# 51.net
KiCad netlist of a schematic drawn in EasyEDA Pro
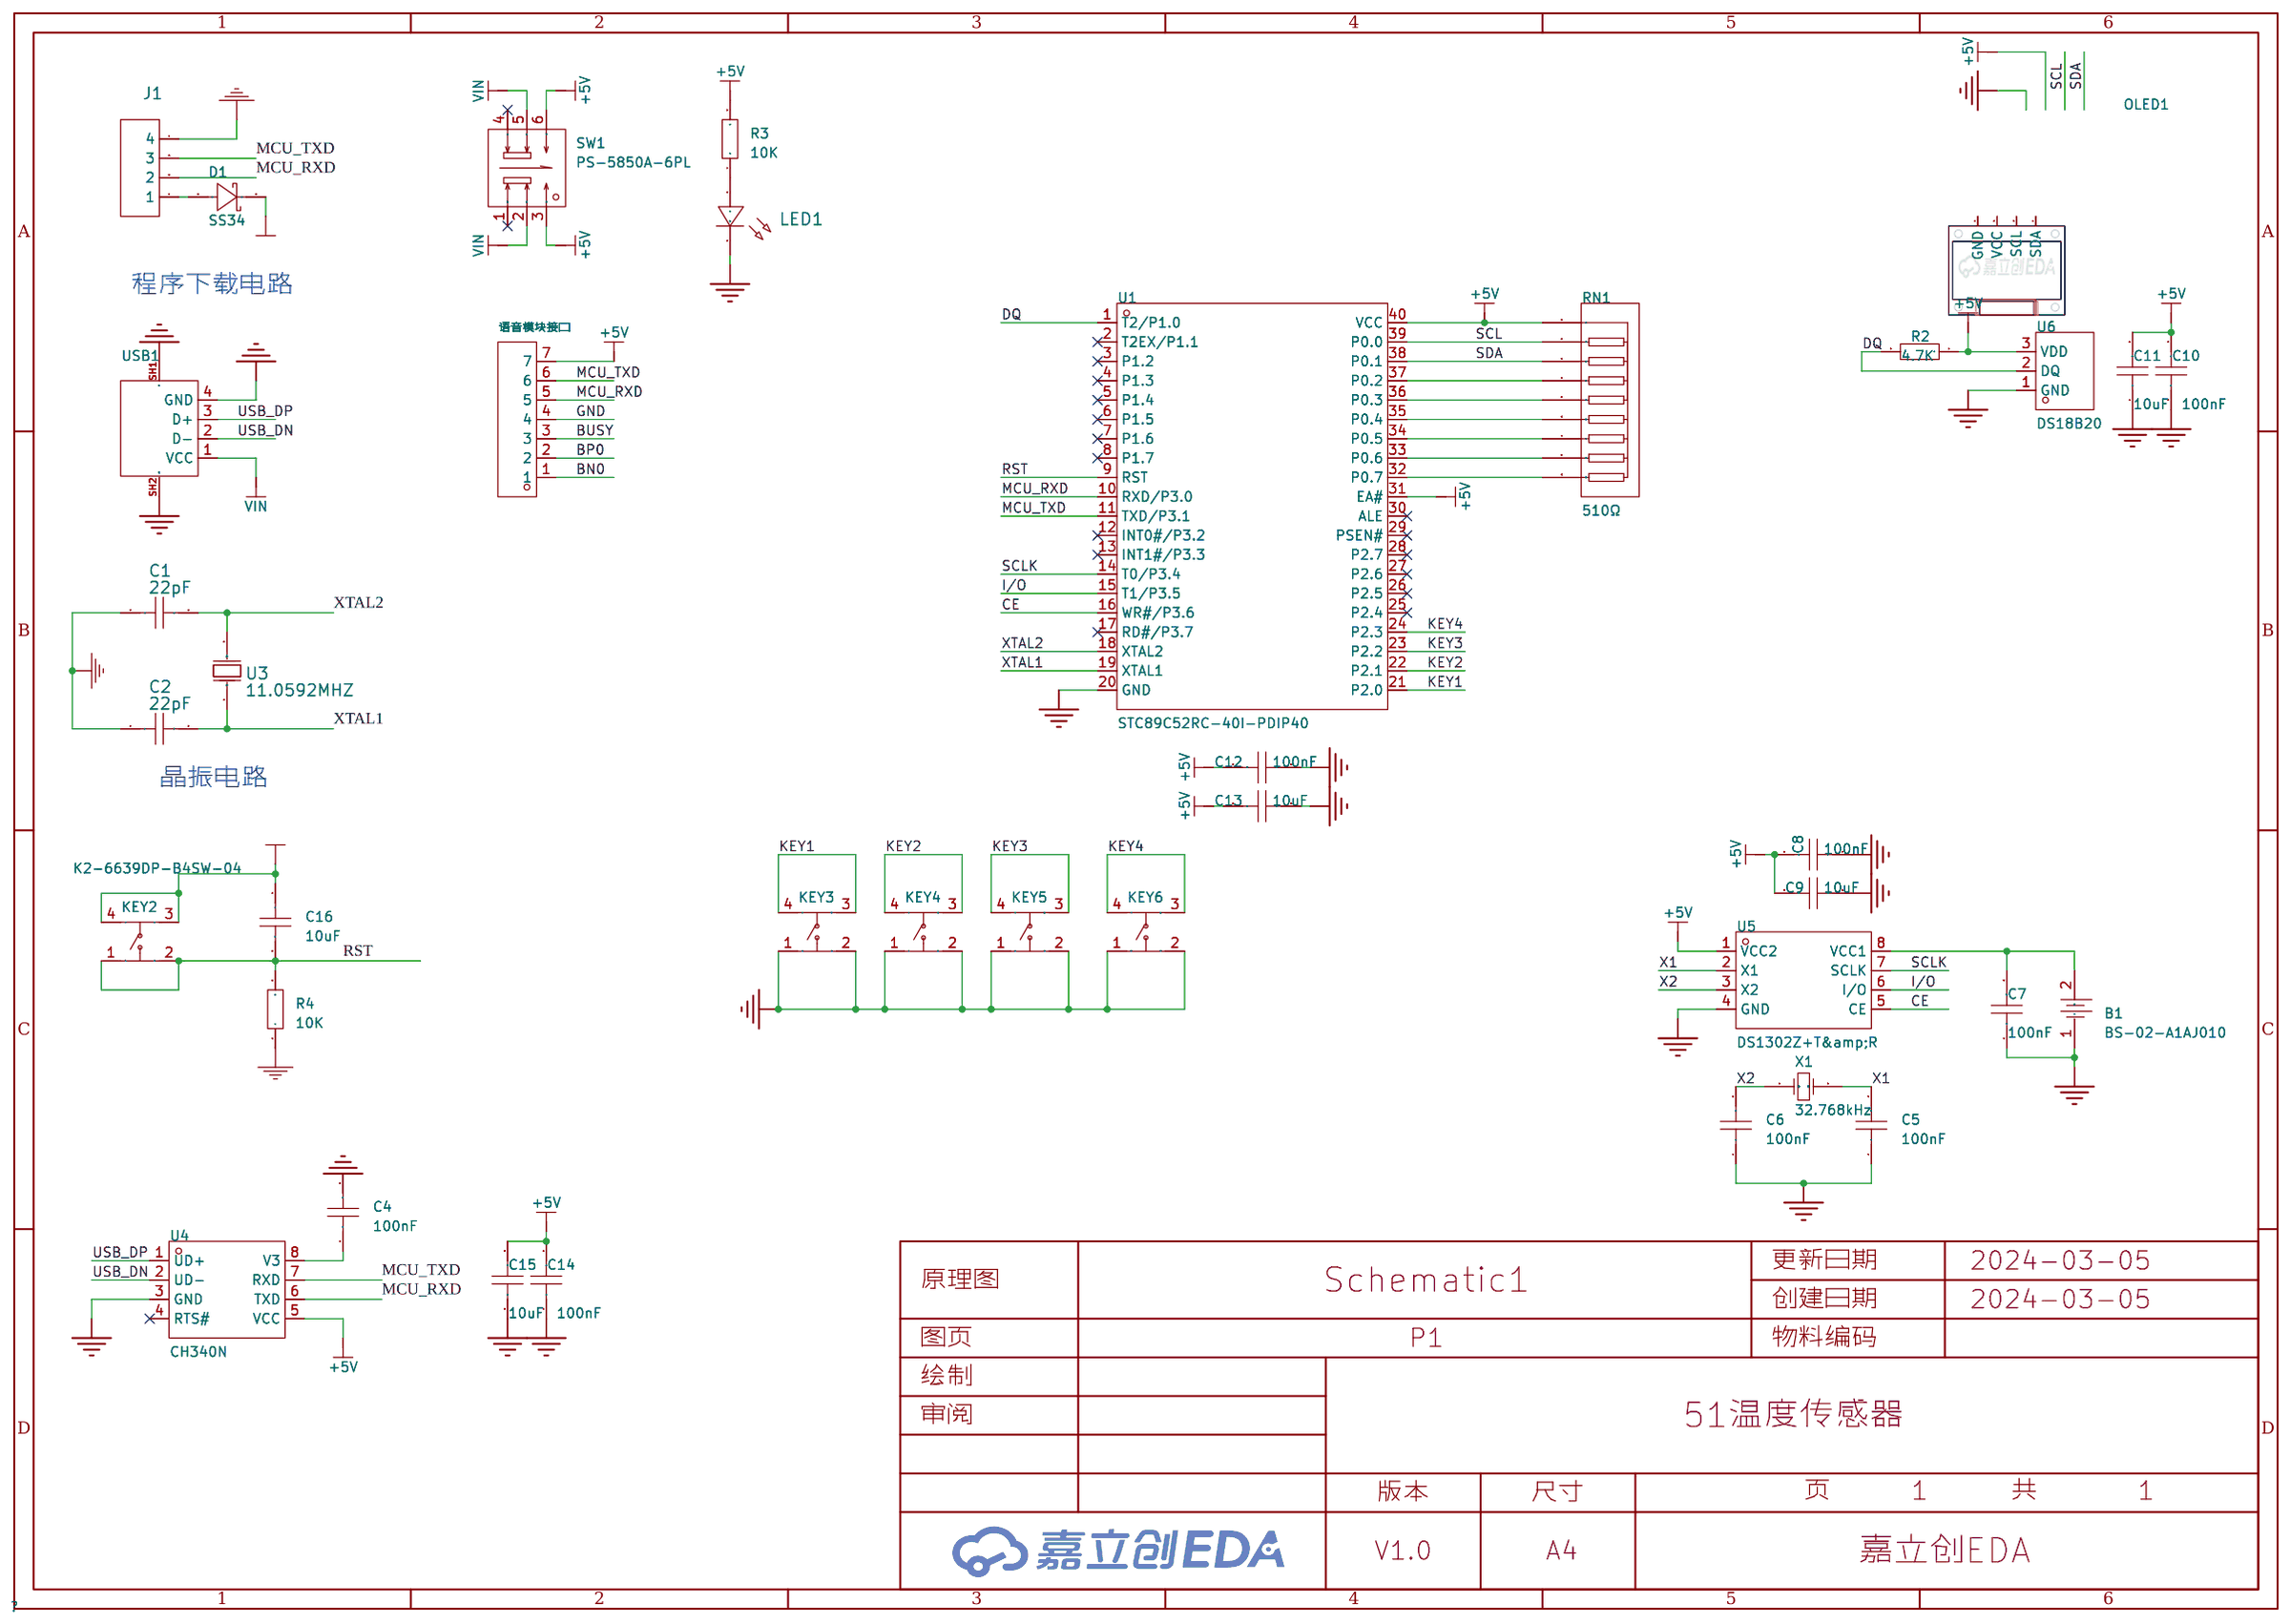
[diagram p0: schematic sheet]

(export (version "E")
  (design (tool "Eeschema 10.0.6"))
  (components
    (comp (ref "B1")
      (value "BS-02-A1AJ010")
      (footprint "easyedapro:BAT-TH_BS-02-A1AJ010")
      (description "连接器类型:电池底座;适用电池规格:CR2032;工作温度范围:-25°C~+85°C;")
      (fields (field (name "Manufacturer") "MYOUNG(美阳)"))
      (libsource (lib "easyedapro") (part "BS-02-A1AJ010"))
    )
    (comp (ref "C1")
      (value "22pF")
      (footprint "easyedapro:C0603")
      (libsource (lib "easyedapro") (part "22pF"))
    )
    (comp (ref "C2")
      (value "22pF")
      (footprint "easyedapro:C0603")
      (libsource (lib "easyedapro") (part "22pF"))
    )
    (comp (ref "C4")
      (value "100nF")
      (footprint "easyedapro:C0603")
      (libsource (lib "easyedapro") (part "CapAcitance"))
    )
    (comp (ref "C5")
      (value "100nF")
      (footprint "easyedapro:C0603")
      (libsource (lib "easyedapro") (part "CapAcitance"))
    )
    (comp (ref "C6")
      (value "100nF")
      (footprint "easyedapro:C0603")
      (libsource (lib "easyedapro") (part "CapAcitance"))
    )
    (comp (ref "C7")
      (value "100nF")
      (footprint "easyedapro:C0603")
      (libsource (lib "easyedapro") (part "CapAcitance"))
    )
    (comp (ref "C8")
      (value "100nF")
      (footprint "easyedapro:C0603")
      (libsource (lib "easyedapro") (part "CapAcitance"))
    )
    (comp (ref "C9")
      (value "10uF")
      (footprint "easyedapro:C0603")
      (libsource (lib "easyedapro") (part "CapAcitance"))
    )
    (comp (ref "C10")
      (value "100nF")
      (footprint "easyedapro:C0603")
      (libsource (lib "easyedapro") (part "CapAcitance"))
    )
    (comp (ref "C11")
      (value "10uF")
      (footprint "easyedapro:C0603")
      (libsource (lib "easyedapro") (part "CapAcitance"))
    )
    (comp (ref "C12")
      (value "100nF")
      (footprint "easyedapro:C0603")
      (libsource (lib "easyedapro") (part "CapAcitance"))
    )
    (comp (ref "C13")
      (value "10uF")
      (footprint "easyedapro:C0603")
      (libsource (lib "easyedapro") (part "CapAcitance"))
    )
    (comp (ref "C14")
      (value "100nF")
      (footprint "easyedapro:C0603")
      (libsource (lib "easyedapro") (part "CapAcitance"))
    )
    (comp (ref "C15")
      (value "10uF")
      (footprint "easyedapro:C0603")
      (libsource (lib "easyedapro") (part "CapAcitance"))
    )
    (comp (ref "C16")
      (value "10uF")
      (footprint "easyedapro:C0603")
      (libsource (lib "easyedapro") (part "CapAcitance"))
    )
    (comp (ref "D1")
      (value "SS34")
      (footprint "easyedapro:SMA_L4.3-W2.5-LS5.0-RD")
      (description "二极管配置:独立式;正向压降(Vf):550mV@3A;直流反向耐压(Vr):40V;平均整流电流(Io):3A;")
      (fields (field (name "Manufacturer") "TWGMC(台湾迪嘉)"))
      (libsource (lib "easyedapro") (part "SS34_C727060"))
    )
    (comp (ref "J1")
      (value "HDR-M-2.54_1x4")
      (footprint "easyedapro:HDR-M-2.54_1X4")
      (libsource (lib "easyedapro") (part "HDR-M-2.54_1x4"))
    )
    (comp (ref "KEY2")
      (value "K2-6639DP-B4SW-04")
      (footprint "easyedapro:KEY-TH_4P-L6.0-W6.0-P3.90-LS7.8")
      (fields (field (name "Manufacturer") "韩国韩荣"))
      (libsource (lib "easyedapro") (part "K2-6639DP-B4SW-04"))
    )
    (comp (ref "KEY3")
      (value "K2-6639DP-B4SW-04")
      (footprint "easyedapro:KEY-TH_4P-L6.0-W6.0-P3.90-LS7.8")
      (fields (field (name "Manufacturer") "韩国韩荣"))
      (libsource (lib "easyedapro") (part "K2-6639DP-B4SW-04"))
    )
    (comp (ref "KEY4")
      (value "K2-6639DP-B4SW-04")
      (footprint "easyedapro:KEY-TH_4P-L6.0-W6.0-P3.90-LS7.8")
      (fields (field (name "Manufacturer") "韩国韩荣"))
      (libsource (lib "easyedapro") (part "K2-6639DP-B4SW-04"))
    )
    (comp (ref "KEY5")
      (value "K2-6639DP-B4SW-04")
      (footprint "easyedapro:KEY-TH_4P-L6.0-W6.0-P3.90-LS7.8")
      (fields (field (name "Manufacturer") "韩国韩荣"))
      (libsource (lib "easyedapro") (part "K2-6639DP-B4SW-04"))
    )
    (comp (ref "KEY6")
      (value "K2-6639DP-B4SW-04")
      (footprint "easyedapro:KEY-TH_4P-L6.0-W6.0-P3.90-LS7.8")
      (fields (field (name "Manufacturer") "韩国韩荣"))
      (libsource (lib "easyedapro") (part "K2-6639DP-B4SW-04"))
    )
    (comp (ref "LED1")
      (value "~")
      (footprint "easyedapro:LED_0603")
      (libsource (lib "easyedapro") (part "LED_R"))
    )
    (comp (ref "OLED1")
      (value "~")
      (footprint "easyedapro:0.96OLED_4P")
      (libsource (lib "easyedapro") (part "0.96OLED模块_4P"))
    )
    (comp (ref "R2") (value "4.7K") (footprint "easyedapro:R0603") (libsource (lib "easyedapro") (part "电阻")))
    (comp (ref "R3") (value "10K") (footprint "easyedapro:R0603") (libsource (lib "easyedapro") (part "电阻")))
    (comp (ref "R4") (value "10K") (footprint "easyedapro:R0603") (libsource (lib "easyedapro") (part "电阻")))
    (comp (ref "RN1")
      (value "510Ω")
      (footprint "easyedapro:RES-ARRAY-TH_9P-P2.54-D1.0")
      (description "电阻器数:8;阻值:510Ω;精度:±5%;单个元件功率:125mW;温度系数:±100ppm/°C;")
      (fields (field (name "Manufacturer Part") "A09-511JP") (field (name "Manufacturer") "FH(风华)"))
      (libsource (lib "easyedapro") (part "A09-511J"))
    )
    (comp (ref "SW1")
      (value "PS-5850A-6PL")
      (footprint "easyedapro:SW-TH_6P-L5.8-W5.8-P2.00-LS4.5-BL")
      (description "5.8自锁按键开关 高头 耐高温")
      (fields (field (name "Manufacturer") "G-Switch(品赞)"))
      (libsource (lib "easyedapro") (part "PS-5850A-6PL"))
    )
    (comp (ref "U1")
      (value "STC89C52RC-40I-PDIP40")
      (footprint "easyedapro:DIP-40_L52.0-W13.7-P2.54-LS15.2-BL")
      (description "CPU内核:51系列;程序存储容量:8KB;RAM总容量:512Byte;GPIO端口数量:35;工作电压范围:3.3V~5.5V;CPU最大主频:-;程序存储器类型:FLASH;")
      (fields (field (name "Manufacturer") "STC(宏晶)"))
      (libsource (lib "easyedapro") (part "STC89C52RC-40I"))
    )
    (comp (ref "U3")
      (value "11.0592MHZ")
      (footprint "easyedapro:HC-49US_L11.5-W4.5-P4.88")
      (fields (field (name "Manufacturer Part") "9B-11.0592MAAJ-B") (field (name "Manufacturer") "TXC(台湾晶技)"))
      (libsource (lib "easyedapro") (part "11.0592MHZ"))
    )
    (comp (ref "U4")
      (value "CH340N")
      (footprint "easyedapro:SOP-8_L5.0-W4.0-P1.27-LS6.0-BL")
      (description "应用功能:-;接口协议:-;")
      (fields (field (name "Manufacturer") "WCH(南京沁恒)"))
      (libsource (lib "easyedapro") (part "CH340N"))
    )
    (comp (ref "U5")
      (value "DS1302Z+T&amp;R")
      (footprint "easyedapro:SOIC-8_L4.9-W3.9-P1.27-LS6.0-BL")
      (description "接口:SPI;")
      (fields (field (name "Manufacturer") "ADI(亚德诺)/MAXIM(美信)"))
      (libsource (lib "easyedapro") (part "DS1302ZN+"))
    )
    (comp (ref "U6")
      (value "DS18B20")
      (footprint "easyedapro:TO-92-3_L4.9-W3.7-P1.27-L")
      (description "温度范围:-55°C~+125°C;精度:±0.4°C;接口类型:-;")
      (fields (field (name "Manufacturer") "MSKSEMI(美森科)"))
      (libsource (lib "easyedapro") (part "DS18B20_C5379069"))
    )
    (comp (ref "USB1")
      (value "~")
      (footprint "easyedapro:USB_ Type-A")
      (libsource (lib "easyedapro") (part "USB_Type-A"))
    )
    (comp (ref "X1")
      (value "32.768kHz")
      (footprint "easyedapro:OSC-TH_BD1.0-P0.50")
      (description "晶振类型:直插晶振;频率:32.768kHz;常温频差:±20ppm;外接负载电容:12.5pF;频率稳定度(全温):±20ppm;")
      (fields (field (name "Manufacturer Part") "K153276812520") (field (name "Manufacturer") "KYX(凯越翔)"))
      (libsource (lib "easyedapro") (part "K153276812520"))
    )
    (comp (ref "语音模块接口")
      (value "~")
      (footprint "easyedapro:HDR-TH_7P-P2.54-V-M")
      (libsource (lib "easyedapro") (part "PZ254V-11-07P"))
    )
  )
  (nets
    (net (code "1") (name "+5V") (class "Default")
      (node (ref "C10") (pin "2") (pinfunction "2_2") (pintype "input"))
      (node (ref "C11") (pin "2") (pinfunction "2_2") (pintype "input"))
      (node (ref "C12") (pin "2") (pinfunction "2_2") (pintype "input"))
      (node (ref "C13") (pin "2") (pinfunction "2_2") (pintype "input"))
      (node (ref "C14") (pin "2") (pinfunction "2_2") (pintype "input"))
      (node (ref "C15") (pin "2") (pinfunction "2_2") (pintype "input"))
      (node (ref "C16") (pin "1") (pinfunction "1_1") (pintype "input"))
      (node (ref "C8") (pin "2") (pinfunction "2_2") (pintype "input"))
      (node (ref "C9") (pin "2") (pinfunction "2_2") (pintype "input"))
      (node (ref "D1") (pin "1") (pinfunction "C_1") (pintype "unspecified"))
      (node (ref "KEY2") (pin "3") (pinfunction "3_3") (pintype "unspecified"))
      (node (ref "KEY2") (pin "4") (pinfunction "4_4") (pintype "unspecified"))
      (node (ref "R2") (pin "1") (pinfunction "1_1") (pintype "input"))
      (node (ref "R3") (pin "2") (pinfunction "2_2") (pintype "input"))
      (node (ref "RN1") (pin "1") (pinfunction "1_1") (pintype "input"))
      (node (ref "SW1") (pin "3") (pinfunction "3_3") (pintype "input"))
      (node (ref "SW1") (pin "6") (pinfunction "6_6") (pintype "input"))
      (node (ref "U1") (pin "31") (pinfunction "EA#_31") (pintype "unspecified"))
      (node (ref "U1") (pin "40") (pinfunction "VCC_40") (pintype "unspecified"))
      (node (ref "U4") (pin "5") (pinfunction "VCC_5") (pintype "unspecified"))
      (node (ref "U5") (pin "1") (pinfunction "VCC2_1") (pintype "unspecified"))
      (node (ref "U6") (pin "3") (pinfunction "VDD_3") (pintype "unspecified"))
      (node (ref "语音模块接口") (pin "7") (pinfunction "7_7") (pintype "input"))
    )
    (net (code "2") (name "/BN0") (class "Default")
      (node (ref "语音模块接口") (pin "1") (pinfunction "1_1") (pintype "input"))
    )
    (net (code "3") (name "/BP0") (class "Default")
      (node (ref "语音模块接口") (pin "2") (pinfunction "2_2") (pintype "input"))
    )
    (net (code "4") (name "/BUSY") (class "Default")
      (node (ref "语音模块接口") (pin "3") (pinfunction "3_3") (pintype "input"))
    )
    (net (code "5") (name "/CE") (class "Default")
      (node (ref "U1") (pin "16") (pinfunction "WR#/P3.6_16") (pintype "unspecified"))
      (node (ref "U5") (pin "5") (pinfunction "CE_5") (pintype "unspecified"))
    )
    (net (code "6") (name "/DQ") (class "Default")
      (node (ref "R2") (pin "2") (pinfunction "2_2") (pintype "input"))
      (node (ref "U1") (pin "1") (pinfunction "T2/P1.0_1") (pintype "unspecified"))
      (node (ref "U6") (pin "2") (pinfunction "DQ_2") (pintype "unspecified"))
    )
    (net (code "7") (name "/I{slash}O") (class "Default")
      (node (ref "U1") (pin "15") (pinfunction "T1/P3.5_15") (pintype "unspecified"))
      (node (ref "U5") (pin "6") (pinfunction "I/O_6") (pintype "unspecified"))
    )
    (net (code "8") (name "/KEY1") (class "Default")
      (node (ref "KEY3") (pin "3") (pinfunction "3_3") (pintype "unspecified"))
      (node (ref "KEY3") (pin "4") (pinfunction "4_4") (pintype "unspecified"))
      (node (ref "U1") (pin "21") (pinfunction "P2.0_21") (pintype "unspecified"))
    )
    (net (code "9") (name "/KEY2") (class "Default")
      (node (ref "KEY4") (pin "3") (pinfunction "3_3") (pintype "unspecified"))
      (node (ref "KEY4") (pin "4") (pinfunction "4_4") (pintype "unspecified"))
      (node (ref "U1") (pin "22") (pinfunction "P2.1_22") (pintype "unspecified"))
    )
    (net (code "10") (name "/KEY3") (class "Default")
      (node (ref "KEY5") (pin "3") (pinfunction "3_3") (pintype "unspecified"))
      (node (ref "KEY5") (pin "4") (pinfunction "4_4") (pintype "unspecified"))
      (node (ref "U1") (pin "23") (pinfunction "P2.2_23") (pintype "unspecified"))
    )
    (net (code "11") (name "/KEY4") (class "Default")
      (node (ref "KEY6") (pin "3") (pinfunction "3_3") (pintype "unspecified"))
      (node (ref "KEY6") (pin "4") (pinfunction "4_4") (pintype "unspecified"))
      (node (ref "U1") (pin "24") (pinfunction "P2.3_24") (pintype "unspecified"))
    )
    (net (code "12") (name "/MCU_RXD") (class "Default")
      (node (ref "J1") (pin "2") (pinfunction "2_2") (pintype "input"))
      (node (ref "U1") (pin "10") (pinfunction "RXD/P3.0_10") (pintype "unspecified"))
      (node (ref "U4") (pin "6") (pinfunction "TXD_6") (pintype "unspecified"))
      (node (ref "语音模块接口") (pin "5") (pinfunction "5_5") (pintype "input"))
    )
    (net (code "13") (name "/MCU_TXD") (class "Default")
      (node (ref "J1") (pin "3") (pinfunction "3_3") (pintype "input"))
      (node (ref "U1") (pin "11") (pinfunction "TXD/P3.1_11") (pintype "unspecified"))
      (node (ref "U4") (pin "7") (pinfunction "RXD_7") (pintype "unspecified"))
      (node (ref "语音模块接口") (pin "6") (pinfunction "6_6") (pintype "input"))
    )
    (net (code "14") (name "/RST") (class "Default")
      (node (ref "C16") (pin "2") (pinfunction "2_2") (pintype "input"))
      (node (ref "KEY2") (pin "1") (pinfunction "1_1") (pintype "unspecified"))
      (node (ref "KEY2") (pin "2") (pinfunction "2_2") (pintype "unspecified"))
      (node (ref "R4") (pin "2") (pinfunction "2_2") (pintype "input"))
      (node (ref "U1") (pin "9") (pinfunction "RST_9") (pintype "unspecified"))
    )
    (net (code "15") (name "/SCL") (class "Default")
      (node (ref "RN1") (pin "2") (pinfunction "2_2") (pintype "input"))
      (node (ref "U1") (pin "39") (pinfunction "P0.0_39") (pintype "unspecified"))
    )
    (net (code "16") (name "/SCLK") (class "Default")
      (node (ref "U1") (pin "14") (pinfunction "T0/P3.4_14") (pintype "unspecified"))
      (node (ref "U5") (pin "7") (pinfunction "SCLK_7") (pintype "unspecified"))
    )
    (net (code "17") (name "/SDA") (class "Default")
      (node (ref "RN1") (pin "3") (pinfunction "3_3") (pintype "input"))
      (node (ref "U1") (pin "38") (pinfunction "P0.1_38") (pintype "unspecified"))
    )
    (net (code "18") (name "/USB_DN") (class "Default")
      (node (ref "U4") (pin "2") (pinfunction "UD-_2") (pintype "unspecified"))
      (node (ref "USB1") (pin "2") (pinfunction "D-_2") (pintype "input"))
    )
    (net (code "19") (name "/USB_DP") (class "Default")
      (node (ref "U4") (pin "1") (pinfunction "UD+_1") (pintype "unspecified"))
      (node (ref "USB1") (pin "3") (pinfunction "D+_3") (pintype "input"))
    )
    (net (code "20") (name "/X1") (class "Default")
      (node (ref "C5") (pin "2") (pinfunction "2_2") (pintype "input"))
      (node (ref "U5") (pin "2") (pinfunction "X1_2") (pintype "unspecified"))
      (node (ref "X1") (pin "2") (pinfunction "OSC2_2") (pintype "unspecified"))
    )
    (net (code "21") (name "/X2") (class "Default")
      (node (ref "C6") (pin "2") (pinfunction "2_2") (pintype "input"))
      (node (ref "U5") (pin "3") (pinfunction "X2_3") (pintype "unspecified"))
      (node (ref "X1") (pin "1") (pinfunction "OSC1_1") (pintype "unspecified"))
    )
    (net (code "22") (name "/XTAL1") (class "Default")
      (node (ref "C2") (pin "2") (pinfunction "2_2") (pintype "input"))
      (node (ref "U1") (pin "19") (pinfunction "XTAL1_19") (pintype "unspecified"))
      (node (ref "U3") (pin "1") (pinfunction "OSC1_1") (pintype "input"))
    )
    (net (code "23") (name "/XTAL2") (class "Default")
      (node (ref "C1") (pin "2") (pinfunction "2_2") (pintype "input"))
      (node (ref "U1") (pin "18") (pinfunction "XTAL2_18") (pintype "unspecified"))
      (node (ref "U3") (pin "2") (pinfunction "OSC2_2") (pintype "input"))
    )
    (net (code "24") (name "GND") (class "Default")
      (node (ref "B1") (pin "1") (pinfunction "1_1") (pintype "input"))
      (node (ref "C1") (pin "1") (pinfunction "1_1") (pintype "input"))
      (node (ref "C10") (pin "1") (pinfunction "1_1") (pintype "input"))
      (node (ref "C11") (pin "1") (pinfunction "1_1") (pintype "input"))
      (node (ref "C12") (pin "1") (pinfunction "1_1") (pintype "input"))
      (node (ref "C13") (pin "1") (pinfunction "1_1") (pintype "input"))
      (node (ref "C14") (pin "1") (pinfunction "1_1") (pintype "input"))
      (node (ref "C15") (pin "1") (pinfunction "1_1") (pintype "input"))
      (node (ref "C2") (pin "1") (pinfunction "1_1") (pintype "input"))
      (node (ref "C4") (pin "2") (pinfunction "2_2") (pintype "input"))
      (node (ref "C5") (pin "1") (pinfunction "1_1") (pintype "input"))
      (node (ref "C6") (pin "1") (pinfunction "1_1") (pintype "input"))
      (node (ref "C7") (pin "1") (pinfunction "1_1") (pintype "input"))
      (node (ref "C8") (pin "1") (pinfunction "1_1") (pintype "input"))
      (node (ref "C9") (pin "1") (pinfunction "1_1") (pintype "input"))
      (node (ref "J1") (pin "4") (pinfunction "4_4") (pintype "input"))
      (node (ref "KEY3") (pin "1") (pinfunction "1_1") (pintype "unspecified"))
      (node (ref "KEY3") (pin "2") (pinfunction "2_2") (pintype "unspecified"))
      (node (ref "KEY4") (pin "1") (pinfunction "1_1") (pintype "unspecified"))
      (node (ref "KEY4") (pin "2") (pinfunction "2_2") (pintype "unspecified"))
      (node (ref "KEY5") (pin "1") (pinfunction "1_1") (pintype "unspecified"))
      (node (ref "KEY5") (pin "2") (pinfunction "2_2") (pintype "unspecified"))
      (node (ref "KEY6") (pin "1") (pinfunction "1_1") (pintype "unspecified"))
      (node (ref "KEY6") (pin "2") (pinfunction "2_2") (pintype "unspecified"))
      (node (ref "LED1") (pin "1") (pinfunction "C_1") (pintype "input"))
      (node (ref "R4") (pin "1") (pinfunction "1_1") (pintype "input"))
      (node (ref "U1") (pin "20") (pinfunction "GND_20") (pintype "unspecified"))
      (node (ref "U4") (pin "3") (pinfunction "GND_3") (pintype "unspecified"))
      (node (ref "U5") (pin "4") (pinfunction "GND_4") (pintype "unspecified"))
      (node (ref "U6") (pin "1") (pinfunction "GND_1") (pintype "unspecified"))
      (node (ref "USB1") (pin "4") (pinfunction "GND_4") (pintype "input"))
      (node (ref "USB1") (pin "SH1") (pinfunction "SH1_SH1") (pintype "input"))
      (node (ref "USB1") (pin "SH2") (pinfunction "SH2_SH2") (pintype "input"))
      (node (ref "语音模块接口") (pin "4") (pinfunction "4_4") (pintype "input"))
    )
    (net (code "25") (name "Net-(D1-A)") (class "Default")
      (node (ref "D1") (pin "2") (pinfunction "A_2") (pintype "unspecified"))
      (node (ref "J1") (pin "1") (pinfunction "1_1") (pintype "input"))
    )
    (net (code "26") (name "Net-(LED1-A)") (class "Default")
      (node (ref "LED1") (pin "2") (pinfunction "A_2") (pintype "input"))
      (node (ref "R3") (pin "1") (pinfunction "1_1") (pintype "input"))
    )
    (net (code "27") (name "Net-(U1-P0.2)") (class "Default")
      (node (ref "RN1") (pin "4") (pinfunction "4_4") (pintype "input"))
      (node (ref "U1") (pin "37") (pinfunction "P0.2_37") (pintype "unspecified"))
    )
    (net (code "28") (name "Net-(U1-P0.3)") (class "Default")
      (node (ref "RN1") (pin "5") (pinfunction "5_5") (pintype "input"))
      (node (ref "U1") (pin "36") (pinfunction "P0.3_36") (pintype "unspecified"))
    )
    (net (code "29") (name "Net-(U1-P0.4)") (class "Default")
      (node (ref "RN1") (pin "6") (pinfunction "6_6") (pintype "input"))
      (node (ref "U1") (pin "35") (pinfunction "P0.4_35") (pintype "unspecified"))
    )
    (net (code "30") (name "Net-(U1-P0.5)") (class "Default")
      (node (ref "RN1") (pin "7") (pinfunction "7_7") (pintype "input"))
      (node (ref "U1") (pin "34") (pinfunction "P0.5_34") (pintype "unspecified"))
    )
    (net (code "31") (name "Net-(U1-P0.6)") (class "Default")
      (node (ref "RN1") (pin "8") (pinfunction "8_8") (pintype "input"))
      (node (ref "U1") (pin "33") (pinfunction "P0.6_33") (pintype "unspecified"))
    )
    (net (code "32") (name "Net-(U1-P0.7)") (class "Default")
      (node (ref "RN1") (pin "9") (pinfunction "9_9") (pintype "input"))
      (node (ref "U1") (pin "32") (pinfunction "P0.7_32") (pintype "unspecified"))
    )
    (net (code "33") (name "Net-(U4-V3)") (class "Default")
      (node (ref "C4") (pin "1") (pinfunction "1_1") (pintype "input"))
      (node (ref "U4") (pin "8") (pinfunction "V3_8") (pintype "unspecified"))
    )
    (net (code "34") (name "Net-(U5-VCC1)") (class "Default")
      (node (ref "B1") (pin "2") (pinfunction "2_2") (pintype "input"))
      (node (ref "C7") (pin "2") (pinfunction "2_2") (pintype "input"))
      (node (ref "U5") (pin "8") (pinfunction "VCC1_8") (pintype "unspecified"))
    )
    (net (code "35") (name "VIN") (class "Default")
      (node (ref "SW1") (pin "2") (pinfunction "2_2") (pintype "input"))
      (node (ref "SW1") (pin "5") (pinfunction "5_5") (pintype "input"))
      (node (ref "USB1") (pin "1") (pinfunction "VCC_1") (pintype "input"))
    )
    (net (code "36") (name "unconnected-(OLED1-GND-Pad1)") (class "Default")
      (node (ref "OLED1") (pin "1") (pinfunction "GND_1") (pintype "input"))
    )
    (net (code "37") (name "unconnected-(OLED1-SCL-Pad3)") (class "Default")
      (node (ref "OLED1") (pin "3") (pinfunction "SCL_3") (pintype "input"))
    )
    (net (code "38") (name "unconnected-(OLED1-SDA-Pad4)") (class "Default")
      (node (ref "OLED1") (pin "4") (pinfunction "SDA_4") (pintype "input"))
    )
    (net (code "39") (name "unconnected-(OLED1-VCC-Pad2)") (class "Default")
      (node (ref "OLED1") (pin "2") (pinfunction "VCC_2") (pintype "input"))
    )
    (net (code "40") (name "unconnected-(SW1-Pad1)") (class "Default")
      (node (ref "SW1") (pin "1") (pinfunction "1_1") (pintype "input+no_connect"))
    )
    (net (code "41") (name "unconnected-(SW1-Pad4)") (class "Default")
      (node (ref "SW1") (pin "4") (pinfunction "4_4") (pintype "input+no_connect"))
    )
    (net (code "42") (name "unconnected-(U1-ALE-Pad30)") (class "Default")
      (node (ref "U1") (pin "30") (pinfunction "ALE_30") (pintype "unspecified+no_connect"))
    )
    (net (code "43") (name "unconnected-(U1-INT0#{slash}P3.2-Pad12)") (class "Default")
      (node (ref "U1") (pin "12") (pinfunction "INT0#/P3.2_12") (pintype "unspecified+no_connect"))
    )
    (net (code "44") (name "unconnected-(U1-INT1#{slash}P3.3-Pad13)") (class "Default")
      (node (ref "U1") (pin "13") (pinfunction "INT1#/P3.3_13") (pintype "unspecified+no_connect"))
    )
    (net (code "45") (name "unconnected-(U1-P1.2-Pad3)") (class "Default")
      (node (ref "U1") (pin "3") (pinfunction "P1.2_3") (pintype "unspecified+no_connect"))
    )
    (net (code "46") (name "unconnected-(U1-P1.3-Pad4)") (class "Default")
      (node (ref "U1") (pin "4") (pinfunction "P1.3_4") (pintype "unspecified+no_connect"))
    )
    (net (code "47") (name "unconnected-(U1-P1.4-Pad5)") (class "Default")
      (node (ref "U1") (pin "5") (pinfunction "P1.4_5") (pintype "unspecified+no_connect"))
    )
    (net (code "48") (name "unconnected-(U1-P1.5-Pad6)") (class "Default")
      (node (ref "U1") (pin "6") (pinfunction "P1.5_6") (pintype "unspecified+no_connect"))
    )
    (net (code "49") (name "unconnected-(U1-P1.6-Pad7)") (class "Default")
      (node (ref "U1") (pin "7") (pinfunction "P1.6_7") (pintype "unspecified+no_connect"))
    )
    (net (code "50") (name "unconnected-(U1-P1.7-Pad8)") (class "Default")
      (node (ref "U1") (pin "8") (pinfunction "P1.7_8") (pintype "unspecified+no_connect"))
    )
    (net (code "51") (name "unconnected-(U1-P2.4-Pad25)") (class "Default")
      (node (ref "U1") (pin "25") (pinfunction "P2.4_25") (pintype "unspecified+no_connect"))
    )
    (net (code "52") (name "unconnected-(U1-P2.5-Pad26)") (class "Default")
      (node (ref "U1") (pin "26") (pinfunction "P2.5_26") (pintype "unspecified+no_connect"))
    )
    (net (code "53") (name "unconnected-(U1-P2.6-Pad27)") (class "Default")
      (node (ref "U1") (pin "27") (pinfunction "P2.6_27") (pintype "unspecified+no_connect"))
    )
    (net (code "54") (name "unconnected-(U1-P2.7-Pad28)") (class "Default")
      (node (ref "U1") (pin "28") (pinfunction "P2.7_28") (pintype "unspecified+no_connect"))
    )
    (net (code "55") (name "unconnected-(U1-PSEN#-Pad29)") (class "Default")
      (node (ref "U1") (pin "29") (pinfunction "PSEN#_29") (pintype "unspecified+no_connect"))
    )
    (net (code "56") (name "unconnected-(U1-RD#{slash}P3.7-Pad17)") (class "Default")
      (node (ref "U1") (pin "17") (pinfunction "RD#/P3.7_17") (pintype "unspecified+no_connect"))
    )
    (net (code "57") (name "unconnected-(U1-T2EX{slash}P1.1-Pad2)") (class "Default")
      (node (ref "U1") (pin "2") (pinfunction "T2EX/P1.1_2") (pintype "unspecified+no_connect"))
    )
    (net (code "58") (name "unconnected-(U4-RTS#-Pad4)") (class "Default")
      (node (ref "U4") (pin "4") (pinfunction "RTS#_4") (pintype "unspecified+no_connect"))
    )
  )
)
